# RPi_Extension_breakout_jetson_alt.net
KiCad netlist of a schematic drawn in EAGLE
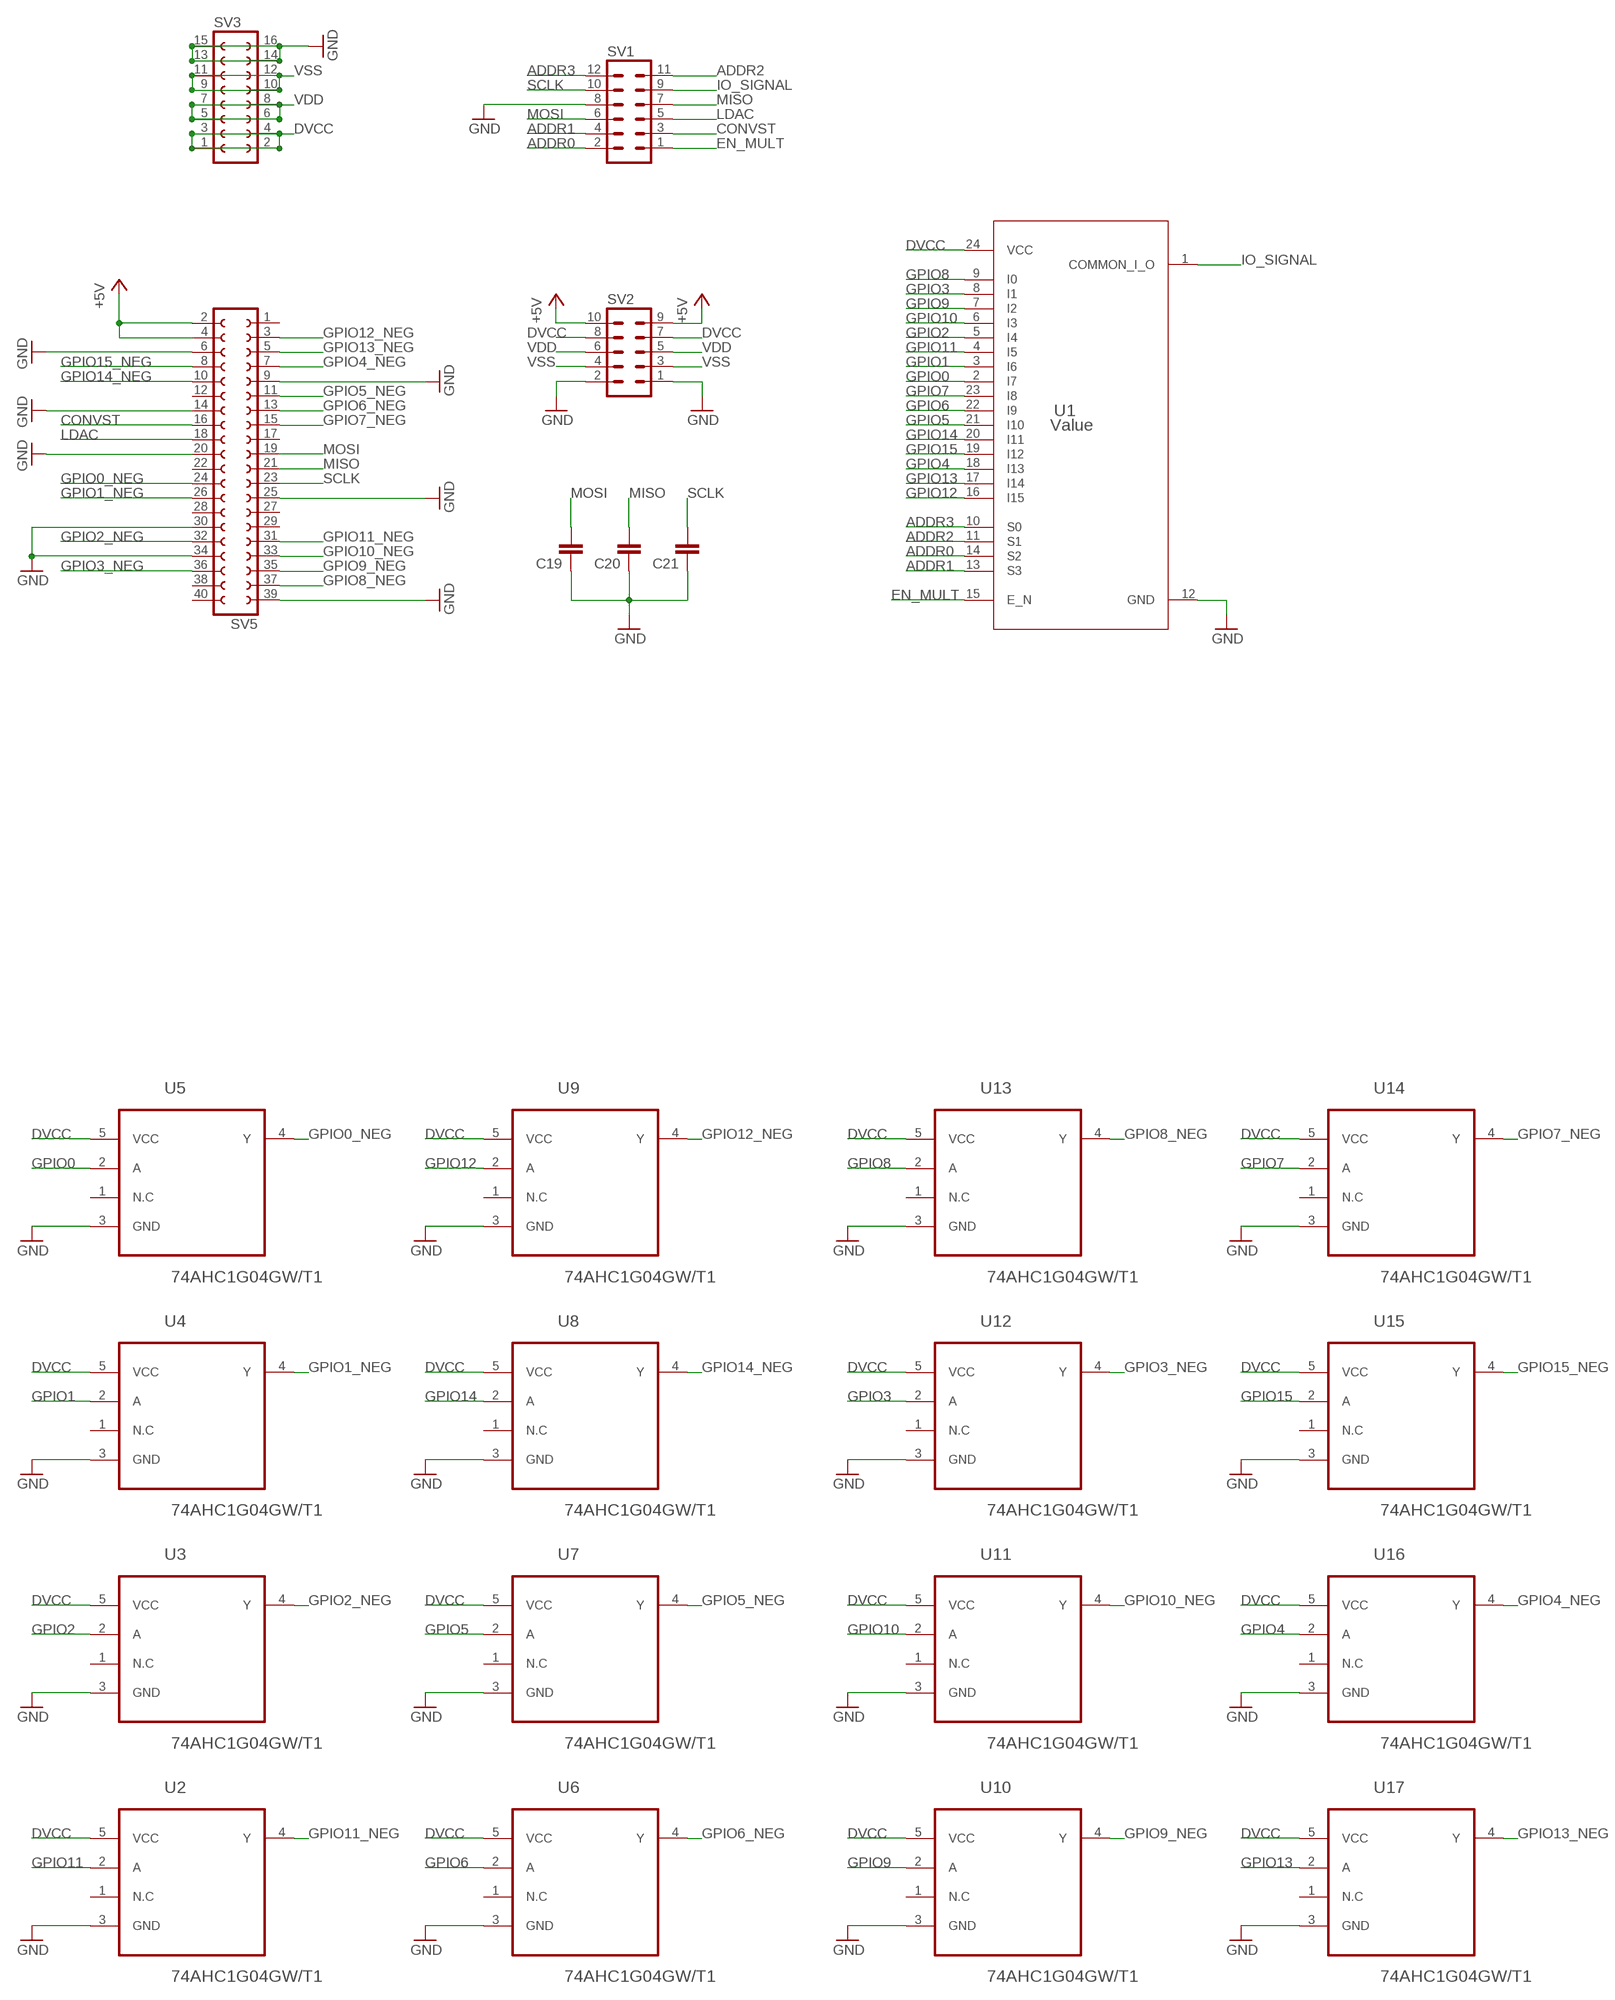
[diagram p0: schematic, sheet 1]

(export (version "E")
  (design (tool "Eeschema 10.0.6"))
  (components
    (comp (ref "C19")
      (value "C-EUC0603")
      (footprint "eagle-import:C0603")
      (libsource (lib "eagle-import") (part "C-EUC0603"))
    )
    (comp (ref "C20")
      (value "C-EUC0603")
      (footprint "eagle-import:C0603")
      (libsource (lib "eagle-import") (part "C-EUC0603"))
    )
    (comp (ref "C21")
      (value "C-EUC0603")
      (footprint "eagle-import:C0603")
      (libsource (lib "eagle-import") (part "C-EUC0603"))
    )
    (comp (ref "SV1")
      (value "MA06-2")
      (footprint "eagle-import:MA06-2")
      (libsource (lib "eagle-import") (part "MA06-2"))
    )
    (comp (ref "SV2")
      (value "MA05-2")
      (footprint "eagle-import:MA05-2")
      (libsource (lib "eagle-import") (part "MA05-2"))
    )
    (comp (ref "SV3")
      (value "FE08-2")
      (footprint "eagle-import:FE08-2")
      (libsource (lib "eagle-import") (part "FE08-2"))
    )
    (comp (ref "SV5")
      (value "FE20-2")
      (footprint "eagle-import:FE20-2")
      (libsource (lib "eagle-import") (part "FE20-2"))
    )
    (comp (ref "U1")
      (value "Value")
      (footprint "eagle-import:DB0024A_N")
      (fields (field (name "MANUFACTURER") "Texas Instruments") (field (name "PARTNUMBER") "CD74HC4067SM96"))
      (libsource (lib "eagle-import") (part "CD74HC4067SM96"))
    )
    (comp (ref "U2")
      (value "74AHC1G04GW/T1")
      (footprint "eagle-import:SOT65P210X110-5N")
      (libsource (lib "eagle-import") (part "74AHC1G04GW/T1"))
    )
    (comp (ref "U3")
      (value "74AHC1G04GW/T1")
      (footprint "eagle-import:SOT65P210X110-5N")
      (libsource (lib "eagle-import") (part "74AHC1G04GW/T1"))
    )
    (comp (ref "U4")
      (value "74AHC1G04GW/T1")
      (footprint "eagle-import:SOT65P210X110-5N")
      (libsource (lib "eagle-import") (part "74AHC1G04GW/T1"))
    )
    (comp (ref "U5")
      (value "74AHC1G04GW/T1")
      (footprint "eagle-import:SOT65P210X110-5N")
      (libsource (lib "eagle-import") (part "74AHC1G04GW/T1"))
    )
    (comp (ref "U6")
      (value "74AHC1G04GW/T1")
      (footprint "eagle-import:SOT65P210X110-5N")
      (libsource (lib "eagle-import") (part "74AHC1G04GW/T1"))
    )
    (comp (ref "U7")
      (value "74AHC1G04GW/T1")
      (footprint "eagle-import:SOT65P210X110-5N")
      (libsource (lib "eagle-import") (part "74AHC1G04GW/T1"))
    )
    (comp (ref "U8")
      (value "74AHC1G04GW/T1")
      (footprint "eagle-import:SOT65P210X110-5N")
      (libsource (lib "eagle-import") (part "74AHC1G04GW/T1"))
    )
    (comp (ref "U9")
      (value "74AHC1G04GW/T1")
      (footprint "eagle-import:SOT65P210X110-5N")
      (libsource (lib "eagle-import") (part "74AHC1G04GW/T1"))
    )
    (comp (ref "U10")
      (value "74AHC1G04GW/T1")
      (footprint "eagle-import:SOT65P210X110-5N")
      (libsource (lib "eagle-import") (part "74AHC1G04GW/T1"))
    )
    (comp (ref "U11")
      (value "74AHC1G04GW/T1")
      (footprint "eagle-import:SOT65P210X110-5N")
      (libsource (lib "eagle-import") (part "74AHC1G04GW/T1"))
    )
    (comp (ref "U12")
      (value "74AHC1G04GW/T1")
      (footprint "eagle-import:SOT65P210X110-5N")
      (libsource (lib "eagle-import") (part "74AHC1G04GW/T1"))
    )
    (comp (ref "U13")
      (value "74AHC1G04GW/T1")
      (footprint "eagle-import:SOT65P210X110-5N")
      (libsource (lib "eagle-import") (part "74AHC1G04GW/T1"))
    )
    (comp (ref "U14")
      (value "74AHC1G04GW/T1")
      (footprint "eagle-import:SOT65P210X110-5N")
      (libsource (lib "eagle-import") (part "74AHC1G04GW/T1"))
    )
    (comp (ref "U15")
      (value "74AHC1G04GW/T1")
      (footprint "eagle-import:SOT65P210X110-5N")
      (libsource (lib "eagle-import") (part "74AHC1G04GW/T1"))
    )
    (comp (ref "U16")
      (value "74AHC1G04GW/T1")
      (footprint "eagle-import:SOT65P210X110-5N")
      (libsource (lib "eagle-import") (part "74AHC1G04GW/T1"))
    )
    (comp (ref "U17")
      (value "74AHC1G04GW/T1")
      (footprint "eagle-import:SOT65P210X110-5N")
      (libsource (lib "eagle-import") (part "74AHC1G04GW/T1"))
    )
  )
  (nets
    (net (code "1") (name "+5V") (class "Default")
      (node (ref "SV2") (pin "10") (pinfunction "10_10") (pintype "passive"))
      (node (ref "SV2") (pin "9") (pinfunction "9_9") (pintype "passive"))
      (node (ref "SV5") (pin "2") (pinfunction "2_2") (pintype "passive"))
      (node (ref "SV5") (pin "4") (pinfunction "4_4") (pintype "passive"))
    )
    (net (code "2") (name "/ADDR0") (class "Default")
      (node (ref "SV1") (pin "2") (pinfunction "2_2") (pintype "passive"))
      (node (ref "U1") (pin "14") (pinfunction "S2_14") (pintype "input"))
    )
    (net (code "3") (name "/ADDR1") (class "Default")
      (node (ref "SV1") (pin "4") (pinfunction "4_4") (pintype "passive"))
      (node (ref "U1") (pin "13") (pinfunction "S3_13") (pintype "input"))
    )
    (net (code "4") (name "/ADDR2") (class "Default")
      (node (ref "SV1") (pin "11") (pinfunction "11_11") (pintype "passive"))
      (node (ref "U1") (pin "11") (pinfunction "S1_11") (pintype "input"))
    )
    (net (code "5") (name "/ADDR3") (class "Default")
      (node (ref "SV1") (pin "12") (pinfunction "12_12") (pintype "passive"))
      (node (ref "U1") (pin "10") (pinfunction "S0_10") (pintype "input"))
    )
    (net (code "6") (name "/CONVST") (class "Default")
      (node (ref "SV1") (pin "3") (pinfunction "3_3") (pintype "passive"))
      (node (ref "SV5") (pin "16") (pinfunction "16_16") (pintype "passive"))
    )
    (net (code "7") (name "/DVCC") (class "Default")
      (node (ref "SV2") (pin "7") (pinfunction "7_7") (pintype "passive"))
      (node (ref "SV2") (pin "8") (pinfunction "8_8") (pintype "passive"))
      (node (ref "SV3") (pin "1") (pinfunction "1_1") (pintype "passive"))
      (node (ref "SV3") (pin "2") (pinfunction "2_2") (pintype "passive"))
      (node (ref "SV3") (pin "3") (pinfunction "3_3") (pintype "passive"))
      (node (ref "SV3") (pin "4") (pinfunction "4_4") (pintype "passive"))
      (node (ref "U1") (pin "24") (pinfunction "VCC_24") (pintype "power_in"))
      (node (ref "U10") (pin "5") (pinfunction "VCC_5") (pintype "power_in"))
      (node (ref "U11") (pin "5") (pinfunction "VCC_5") (pintype "power_in"))
      (node (ref "U12") (pin "5") (pinfunction "VCC_5") (pintype "power_in"))
      (node (ref "U13") (pin "5") (pinfunction "VCC_5") (pintype "power_in"))
      (node (ref "U14") (pin "5") (pinfunction "VCC_5") (pintype "power_in"))
      (node (ref "U15") (pin "5") (pinfunction "VCC_5") (pintype "power_in"))
      (node (ref "U16") (pin "5") (pinfunction "VCC_5") (pintype "power_in"))
      (node (ref "U17") (pin "5") (pinfunction "VCC_5") (pintype "power_in"))
      (node (ref "U2") (pin "5") (pinfunction "VCC_5") (pintype "power_in"))
      (node (ref "U3") (pin "5") (pinfunction "VCC_5") (pintype "power_in"))
      (node (ref "U4") (pin "5") (pinfunction "VCC_5") (pintype "power_in"))
      (node (ref "U5") (pin "5") (pinfunction "VCC_5") (pintype "power_in"))
      (node (ref "U6") (pin "5") (pinfunction "VCC_5") (pintype "power_in"))
      (node (ref "U7") (pin "5") (pinfunction "VCC_5") (pintype "power_in"))
      (node (ref "U8") (pin "5") (pinfunction "VCC_5") (pintype "power_in"))
      (node (ref "U9") (pin "5") (pinfunction "VCC_5") (pintype "power_in"))
    )
    (net (code "8") (name "/EN_MULT") (class "Default")
      (node (ref "SV1") (pin "1") (pinfunction "1_1") (pintype "passive"))
      (node (ref "U1") (pin "15") (pinfunction "E_N_15") (pintype "input"))
    )
    (net (code "9") (name "/GPIO0") (class "Default")
      (node (ref "U1") (pin "2") (pinfunction "I7_2") (pintype "input"))
      (node (ref "U5") (pin "2") (pinfunction "A_2") (pintype "input"))
    )
    (net (code "10") (name "/GPIO0_NEG") (class "Default")
      (node (ref "SV5") (pin "24") (pinfunction "24_24") (pintype "passive"))
      (node (ref "U5") (pin "4") (pinfunction "Y_4") (pintype "output"))
    )
    (net (code "11") (name "/GPIO1") (class "Default")
      (node (ref "U1") (pin "3") (pinfunction "I6_3") (pintype "input"))
      (node (ref "U4") (pin "2") (pinfunction "A_2") (pintype "input"))
    )
    (net (code "12") (name "/GPIO1_NEG") (class "Default")
      (node (ref "SV5") (pin "26") (pinfunction "26_26") (pintype "passive"))
      (node (ref "U4") (pin "4") (pinfunction "Y_4") (pintype "output"))
    )
    (net (code "13") (name "/GPIO2") (class "Default")
      (node (ref "U1") (pin "5") (pinfunction "I4_5") (pintype "input"))
      (node (ref "U3") (pin "2") (pinfunction "A_2") (pintype "input"))
    )
    (net (code "14") (name "/GPIO2_NEG") (class "Default")
      (node (ref "SV5") (pin "32") (pinfunction "32_32") (pintype "passive"))
      (node (ref "U3") (pin "4") (pinfunction "Y_4") (pintype "output"))
    )
    (net (code "15") (name "/GPIO3") (class "Default")
      (node (ref "U1") (pin "8") (pinfunction "I1_8") (pintype "input"))
      (node (ref "U12") (pin "2") (pinfunction "A_2") (pintype "input"))
    )
    (net (code "16") (name "/GPIO3_NEG") (class "Default")
      (node (ref "SV5") (pin "36") (pinfunction "36_36") (pintype "passive"))
      (node (ref "U12") (pin "4") (pinfunction "Y_4") (pintype "output"))
    )
    (net (code "17") (name "/GPIO4") (class "Default")
      (node (ref "U1") (pin "18") (pinfunction "I13_18") (pintype "input"))
      (node (ref "U16") (pin "2") (pinfunction "A_2") (pintype "input"))
    )
    (net (code "18") (name "/GPIO4_NEG") (class "Default")
      (node (ref "SV5") (pin "7") (pinfunction "7_7") (pintype "passive"))
      (node (ref "U16") (pin "4") (pinfunction "Y_4") (pintype "output"))
    )
    (net (code "19") (name "/GPIO5") (class "Default")
      (node (ref "U1") (pin "21") (pinfunction "I10_21") (pintype "input"))
      (node (ref "U7") (pin "2") (pinfunction "A_2") (pintype "input"))
    )
    (net (code "20") (name "/GPIO5_NEG") (class "Default")
      (node (ref "SV5") (pin "11") (pinfunction "11_11") (pintype "passive"))
      (node (ref "U7") (pin "4") (pinfunction "Y_4") (pintype "output"))
    )
    (net (code "21") (name "/GPIO6") (class "Default")
      (node (ref "U1") (pin "22") (pinfunction "I9_22") (pintype "input"))
      (node (ref "U6") (pin "2") (pinfunction "A_2") (pintype "input"))
    )
    (net (code "22") (name "/GPIO6_NEG") (class "Default")
      (node (ref "SV5") (pin "13") (pinfunction "13_13") (pintype "passive"))
      (node (ref "U6") (pin "4") (pinfunction "Y_4") (pintype "output"))
    )
    (net (code "23") (name "/GPIO7") (class "Default")
      (node (ref "U1") (pin "23") (pinfunction "I8_23") (pintype "input"))
      (node (ref "U14") (pin "2") (pinfunction "A_2") (pintype "input"))
    )
    (net (code "24") (name "/GPIO7_NEG") (class "Default")
      (node (ref "SV5") (pin "15") (pinfunction "15_15") (pintype "passive"))
      (node (ref "U14") (pin "4") (pinfunction "Y_4") (pintype "output"))
    )
    (net (code "25") (name "/GPIO8") (class "Default")
      (node (ref "U1") (pin "9") (pinfunction "I0_9") (pintype "input"))
      (node (ref "U13") (pin "2") (pinfunction "A_2") (pintype "input"))
    )
    (net (code "26") (name "/GPIO8_NEG") (class "Default")
      (node (ref "SV5") (pin "37") (pinfunction "37_37") (pintype "passive"))
      (node (ref "U13") (pin "4") (pinfunction "Y_4") (pintype "output"))
    )
    (net (code "27") (name "/GPIO9") (class "Default")
      (node (ref "U1") (pin "7") (pinfunction "I2_7") (pintype "input"))
      (node (ref "U10") (pin "2") (pinfunction "A_2") (pintype "input"))
    )
    (net (code "28") (name "/GPIO9_NEG") (class "Default")
      (node (ref "SV5") (pin "35") (pinfunction "35_35") (pintype "passive"))
      (node (ref "U10") (pin "4") (pinfunction "Y_4") (pintype "output"))
    )
    (net (code "29") (name "/GPIO10") (class "Default")
      (node (ref "U1") (pin "6") (pinfunction "I3_6") (pintype "input"))
      (node (ref "U11") (pin "2") (pinfunction "A_2") (pintype "input"))
    )
    (net (code "30") (name "/GPIO10_NEG") (class "Default")
      (node (ref "SV5") (pin "33") (pinfunction "33_33") (pintype "passive"))
      (node (ref "U11") (pin "4") (pinfunction "Y_4") (pintype "output"))
    )
    (net (code "31") (name "/GPIO11") (class "Default")
      (node (ref "U1") (pin "4") (pinfunction "I5_4") (pintype "input"))
      (node (ref "U2") (pin "2") (pinfunction "A_2") (pintype "input"))
    )
    (net (code "32") (name "/GPIO11_NEG") (class "Default")
      (node (ref "SV5") (pin "31") (pinfunction "31_31") (pintype "passive"))
      (node (ref "U2") (pin "4") (pinfunction "Y_4") (pintype "output"))
    )
    (net (code "33") (name "/GPIO12") (class "Default")
      (node (ref "U1") (pin "16") (pinfunction "I15_16") (pintype "input"))
      (node (ref "U9") (pin "2") (pinfunction "A_2") (pintype "input"))
    )
    (net (code "34") (name "/GPIO12_NEG") (class "Default")
      (node (ref "SV5") (pin "3") (pinfunction "3_3") (pintype "passive"))
      (node (ref "U9") (pin "4") (pinfunction "Y_4") (pintype "output"))
    )
    (net (code "35") (name "/GPIO13") (class "Default")
      (node (ref "U1") (pin "17") (pinfunction "I14_17") (pintype "input"))
      (node (ref "U17") (pin "2") (pinfunction "A_2") (pintype "input"))
    )
    (net (code "36") (name "/GPIO13_NEG") (class "Default")
      (node (ref "SV5") (pin "5") (pinfunction "5_5") (pintype "passive"))
      (node (ref "U17") (pin "4") (pinfunction "Y_4") (pintype "output"))
    )
    (net (code "37") (name "/GPIO14") (class "Default")
      (node (ref "U1") (pin "20") (pinfunction "I11_20") (pintype "input"))
      (node (ref "U8") (pin "2") (pinfunction "A_2") (pintype "input"))
    )
    (net (code "38") (name "/GPIO14_NEG") (class "Default")
      (node (ref "SV5") (pin "10") (pinfunction "10_10") (pintype "passive"))
      (node (ref "U8") (pin "4") (pinfunction "Y_4") (pintype "output"))
    )
    (net (code "39") (name "/GPIO15") (class "Default")
      (node (ref "U1") (pin "19") (pinfunction "I12_19") (pintype "input"))
      (node (ref "U15") (pin "2") (pinfunction "A_2") (pintype "input"))
    )
    (net (code "40") (name "/GPIO15_NEG") (class "Default")
      (node (ref "SV5") (pin "8") (pinfunction "8_8") (pintype "passive"))
      (node (ref "U15") (pin "4") (pinfunction "Y_4") (pintype "output"))
    )
    (net (code "41") (name "/IO_SIGNAL") (class "Default")
      (node (ref "SV1") (pin "9") (pinfunction "9_9") (pintype "passive"))
      (node (ref "U1") (pin "1") (pinfunction "COMMON_I_O_1") (pintype "bidirectional"))
    )
    (net (code "42") (name "/LDAC") (class "Default")
      (node (ref "SV1") (pin "5") (pinfunction "5_5") (pintype "passive"))
      (node (ref "SV5") (pin "18") (pinfunction "18_18") (pintype "passive"))
    )
    (net (code "43") (name "/MISO") (class "Default")
      (node (ref "C20") (pin "2") (pinfunction "2_2") (pintype "passive"))
      (node (ref "SV1") (pin "7") (pinfunction "7_7") (pintype "passive"))
      (node (ref "SV5") (pin "21") (pinfunction "21_21") (pintype "passive"))
    )
    (net (code "44") (name "/MOSI") (class "Default")
      (node (ref "C19") (pin "2") (pinfunction "2_2") (pintype "passive"))
      (node (ref "SV1") (pin "6") (pinfunction "6_6") (pintype "passive"))
      (node (ref "SV5") (pin "19") (pinfunction "19_19") (pintype "passive"))
    )
    (net (code "45") (name "/SCLK") (class "Default")
      (node (ref "C21") (pin "2") (pinfunction "2_2") (pintype "passive"))
      (node (ref "SV1") (pin "10") (pinfunction "10_10") (pintype "passive"))
      (node (ref "SV5") (pin "23") (pinfunction "23_23") (pintype "passive"))
    )
    (net (code "46") (name "/VDD") (class "Default")
      (node (ref "SV2") (pin "5") (pinfunction "5_5") (pintype "passive"))
      (node (ref "SV2") (pin "6") (pinfunction "6_6") (pintype "passive"))
      (node (ref "SV3") (pin "5") (pinfunction "5_5") (pintype "passive"))
      (node (ref "SV3") (pin "6") (pinfunction "6_6") (pintype "passive"))
      (node (ref "SV3") (pin "7") (pinfunction "7_7") (pintype "passive"))
      (node (ref "SV3") (pin "8") (pinfunction "8_8") (pintype "passive"))
    )
    (net (code "47") (name "/VSS") (class "Default")
      (node (ref "SV2") (pin "3") (pinfunction "3_3") (pintype "passive"))
      (node (ref "SV2") (pin "4") (pinfunction "4_4") (pintype "passive"))
      (node (ref "SV3") (pin "10") (pinfunction "10_10") (pintype "passive"))
      (node (ref "SV3") (pin "11") (pinfunction "11_11") (pintype "passive"))
      (node (ref "SV3") (pin "12") (pinfunction "12_12") (pintype "passive"))
      (node (ref "SV3") (pin "9") (pinfunction "9_9") (pintype "passive"))
    )
    (net (code "48") (name "GND") (class "Default")
      (node (ref "C19") (pin "1") (pinfunction "1_1") (pintype "passive"))
      (node (ref "C20") (pin "1") (pinfunction "1_1") (pintype "passive"))
      (node (ref "C21") (pin "1") (pinfunction "1_1") (pintype "passive"))
      (node (ref "SV1") (pin "8") (pinfunction "8_8") (pintype "passive"))
      (node (ref "SV2") (pin "1") (pinfunction "1_1") (pintype "passive"))
      (node (ref "SV2") (pin "2") (pinfunction "2_2") (pintype "passive"))
      (node (ref "SV3") (pin "13") (pinfunction "13_13") (pintype "passive"))
      (node (ref "SV3") (pin "14") (pinfunction "14_14") (pintype "passive"))
      (node (ref "SV3") (pin "15") (pinfunction "15_15") (pintype "passive"))
      (node (ref "SV3") (pin "16") (pinfunction "16_16") (pintype "passive"))
      (node (ref "SV5") (pin "14") (pinfunction "14_14") (pintype "passive"))
      (node (ref "SV5") (pin "20") (pinfunction "20_20") (pintype "passive"))
      (node (ref "SV5") (pin "25") (pinfunction "25_25") (pintype "passive"))
      (node (ref "SV5") (pin "30") (pinfunction "30_30") (pintype "passive"))
      (node (ref "SV5") (pin "34") (pinfunction "34_34") (pintype "passive"))
      (node (ref "SV5") (pin "39") (pinfunction "39_39") (pintype "passive"))
      (node (ref "SV5") (pin "6") (pinfunction "6_6") (pintype "passive"))
      (node (ref "SV5") (pin "9") (pinfunction "9_9") (pintype "passive"))
      (node (ref "U1") (pin "12") (pinfunction "GND_12") (pintype "power_in"))
      (node (ref "U10") (pin "3") (pinfunction "GND_3") (pintype "passive"))
      (node (ref "U11") (pin "3") (pinfunction "GND_3") (pintype "passive"))
      (node (ref "U12") (pin "3") (pinfunction "GND_3") (pintype "passive"))
      (node (ref "U13") (pin "3") (pinfunction "GND_3") (pintype "passive"))
      (node (ref "U14") (pin "3") (pinfunction "GND_3") (pintype "passive"))
      (node (ref "U15") (pin "3") (pinfunction "GND_3") (pintype "passive"))
      (node (ref "U16") (pin "3") (pinfunction "GND_3") (pintype "passive"))
      (node (ref "U17") (pin "3") (pinfunction "GND_3") (pintype "passive"))
      (node (ref "U2") (pin "3") (pinfunction "GND_3") (pintype "passive"))
      (node (ref "U3") (pin "3") (pinfunction "GND_3") (pintype "passive"))
      (node (ref "U4") (pin "3") (pinfunction "GND_3") (pintype "passive"))
      (node (ref "U5") (pin "3") (pinfunction "GND_3") (pintype "passive"))
      (node (ref "U6") (pin "3") (pinfunction "GND_3") (pintype "passive"))
      (node (ref "U7") (pin "3") (pinfunction "GND_3") (pintype "passive"))
      (node (ref "U8") (pin "3") (pinfunction "GND_3") (pintype "passive"))
      (node (ref "U9") (pin "3") (pinfunction "GND_3") (pintype "passive"))
    )
    (net (code "49") (name "unconnected-(SV5-Pad1)") (class "Default")
      (node (ref "SV5") (pin "1") (pinfunction "1_1") (pintype "passive"))
    )
    (net (code "50") (name "unconnected-(SV5-Pad12)") (class "Default")
      (node (ref "SV5") (pin "12") (pinfunction "12_12") (pintype "passive"))
    )
    (net (code "51") (name "unconnected-(SV5-Pad17)") (class "Default")
      (node (ref "SV5") (pin "17") (pinfunction "17_17") (pintype "passive"))
    )
    (net (code "52") (name "unconnected-(SV5-Pad22)") (class "Default")
      (node (ref "SV5") (pin "22") (pinfunction "22_22") (pintype "passive"))
    )
    (net (code "53") (name "unconnected-(SV5-Pad27)") (class "Default")
      (node (ref "SV5") (pin "27") (pinfunction "27_27") (pintype "passive"))
    )
    (net (code "54") (name "unconnected-(SV5-Pad28)") (class "Default")
      (node (ref "SV5") (pin "28") (pinfunction "28_28") (pintype "passive"))
    )
    (net (code "55") (name "unconnected-(SV5-Pad29)") (class "Default")
      (node (ref "SV5") (pin "29") (pinfunction "29_29") (pintype "passive"))
    )
    (net (code "56") (name "unconnected-(SV5-Pad38)") (class "Default")
      (node (ref "SV5") (pin "38") (pinfunction "38_38") (pintype "passive"))
    )
    (net (code "57") (name "unconnected-(SV5-Pad40)") (class "Default")
      (node (ref "SV5") (pin "40") (pinfunction "40_40") (pintype "passive"))
    )
    (net (code "58") (name "unconnected-(U2-N.C-Pad1)") (class "Default")
      (node (ref "U2") (pin "1") (pinfunction "N.C_1") (pintype "no_connect"))
    )
    (net (code "59") (name "unconnected-(U3-N.C-Pad1)") (class "Default")
      (node (ref "U3") (pin "1") (pinfunction "N.C_1") (pintype "no_connect"))
    )
    (net (code "60") (name "unconnected-(U4-N.C-Pad1)") (class "Default")
      (node (ref "U4") (pin "1") (pinfunction "N.C_1") (pintype "no_connect"))
    )
    (net (code "61") (name "unconnected-(U5-N.C-Pad1)") (class "Default")
      (node (ref "U5") (pin "1") (pinfunction "N.C_1") (pintype "no_connect"))
    )
    (net (code "62") (name "unconnected-(U6-N.C-Pad1)") (class "Default")
      (node (ref "U6") (pin "1") (pinfunction "N.C_1") (pintype "no_connect"))
    )
    (net (code "63") (name "unconnected-(U7-N.C-Pad1)") (class "Default")
      (node (ref "U7") (pin "1") (pinfunction "N.C_1") (pintype "no_connect"))
    )
    (net (code "64") (name "unconnected-(U8-N.C-Pad1)") (class "Default")
      (node (ref "U8") (pin "1") (pinfunction "N.C_1") (pintype "no_connect"))
    )
    (net (code "65") (name "unconnected-(U9-N.C-Pad1)") (class "Default")
      (node (ref "U9") (pin "1") (pinfunction "N.C_1") (pintype "no_connect"))
    )
    (net (code "66") (name "unconnected-(U10-N.C-Pad1)") (class "Default")
      (node (ref "U10") (pin "1") (pinfunction "N.C_1") (pintype "no_connect"))
    )
    (net (code "67") (name "unconnected-(U11-N.C-Pad1)") (class "Default")
      (node (ref "U11") (pin "1") (pinfunction "N.C_1") (pintype "no_connect"))
    )
    (net (code "68") (name "unconnected-(U12-N.C-Pad1)") (class "Default")
      (node (ref "U12") (pin "1") (pinfunction "N.C_1") (pintype "no_connect"))
    )
    (net (code "69") (name "unconnected-(U13-N.C-Pad1)") (class "Default")
      (node (ref "U13") (pin "1") (pinfunction "N.C_1") (pintype "no_connect"))
    )
    (net (code "70") (name "unconnected-(U14-N.C-Pad1)") (class "Default")
      (node (ref "U14") (pin "1") (pinfunction "N.C_1") (pintype "no_connect"))
    )
    (net (code "71") (name "unconnected-(U15-N.C-Pad1)") (class "Default")
      (node (ref "U15") (pin "1") (pinfunction "N.C_1") (pintype "no_connect"))
    )
    (net (code "72") (name "unconnected-(U16-N.C-Pad1)") (class "Default")
      (node (ref "U16") (pin "1") (pinfunction "N.C_1") (pintype "no_connect"))
    )
    (net (code "73") (name "unconnected-(U17-N.C-Pad1)") (class "Default")
      (node (ref "U17") (pin "1") (pinfunction "N.C_1") (pintype "no_connect"))
    )
  )
)
